# Volt_Measurement.net
KiCad netlist of a schematic drawn in Altium Designer
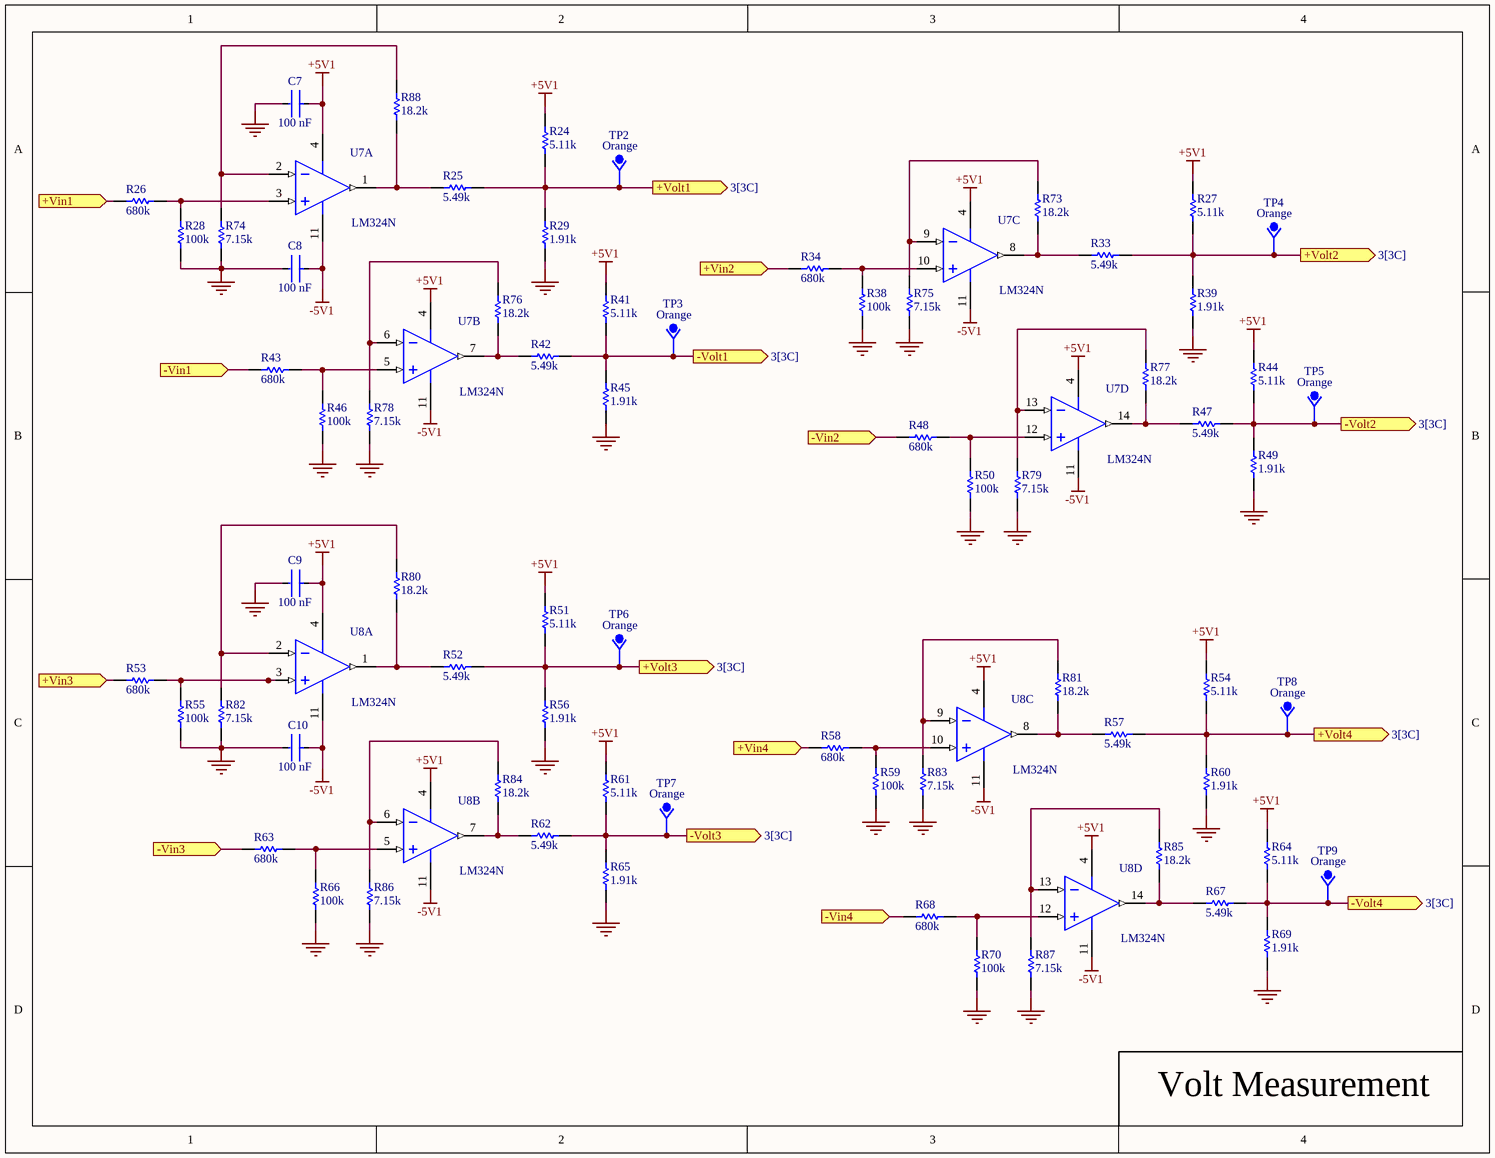
[diagram p0: Volt_Measurement.SchDoc]

(export (version "E")
  (design (tool "Eeschema 10.0.6"))
  (components
    (comp (ref "C7")
      (value "100 nF")
      (footprint "FP-CC0805-0_85-MFG")
      (description "CAP CER 0.1UF 16V X7R 0805")
      (fields
        (field (name "MANUFACTURER PART NUMBER") "CC0805KRX7R7BB104")
        (field (name "MANUFACTURER") "Yageo")
      )
      (libsource (lib "Altium Content Vault") (part "11868f565c42a9108669ba33697ecf6"))
    )
    (comp (ref "C8")
      (value "100 nF")
      (footprint "FP-CC0805-0_85-MFG")
      (description "CAP CER 0.1UF 16V X7R 0805")
      (fields
        (field (name "MANUFACTURER PART NUMBER") "CC0805KRX7R7BB104")
        (field (name "MANUFACTURER") "Yageo")
      )
      (libsource (lib "Altium Content Vault") (part "11868f565c42a9108669ba33697ecf6"))
    )
    (comp (ref "C9")
      (value "100 nF")
      (footprint "FP-CC0805-0_85-MFG")
      (description "CAP CER 0.1UF 16V X7R 0805")
      (fields
        (field (name "MANUFACTURER PART NUMBER") "CC0805KRX7R7BB104")
        (field (name "MANUFACTURER") "Yageo")
      )
      (libsource (lib "Altium Content Vault") (part "11868f565c42a9108669ba33697ecf6"))
    )
    (comp (ref "C10")
      (value "100 nF")
      (footprint "FP-CC0805-0_85-MFG")
      (description "CAP CER 0.1UF 16V X7R 0805")
      (fields
        (field (name "MANUFACTURER PART NUMBER") "CC0805KRX7R7BB104")
        (field (name "MANUFACTURER") "Yageo")
      )
      (libsource (lib "Altium Content Vault") (part "11868f565c42a9108669ba33697ecf6"))
    )
    (comp (ref "R24")
      (value "5.11k")
      (footprint "0805 Res")
      (fields
        (field (name "MANUFACTURER") "Stackpole Electronics")
        (field (name "MANUFACTURER PART NUMBER") "RMCF0805FT5K11")
        (field (name "TOLERANCE") "1%")
        (field (name "PUBLISHER") "Altium Limited")
      )
      (libsource (lib "Miscellaneous Devices") (part "Res1"))
    )
    (comp (ref "R25")
      (value "5.49k")
      (footprint "0805 Res")
      (fields
        (field (name "MANUFACTURER") "Stackpole Electronics")
        (field (name "MANUFACTURER PART NUMBER") "RMCF0805FT5K49")
        (field (name "TOLERANCE") "1%")
        (field (name "PUBLISHER") "Altium Limited")
      )
      (libsource (lib "Miscellaneous Devices") (part "Res1"))
    )
    (comp (ref "R26")
      (value "680k")
      (footprint "0805 Res")
      (fields
        (field (name "MANUFACTURER") "Stackpole Electronics")
        (field (name "MANUFACTURER PART NUMBER") "RMCF0805FT680K")
        (field (name "TOLERANCE") "1%")
        (field (name "PUBLISHER") "Altium Limited")
      )
      (libsource (lib "Miscellaneous Devices") (part "Res1"))
    )
    (comp (ref "R27")
      (value "5.11k")
      (footprint "0805 Res")
      (fields
        (field (name "MANUFACTURER") "Stackpole Electronics")
        (field (name "MANUFACTURER PART NUMBER") "RMCF0805FT5K11")
        (field (name "TOLERANCE") "1%")
        (field (name "PUBLISHER") "Altium Limited")
      )
      (libsource (lib "Miscellaneous Devices") (part "Res1"))
    )
    (comp (ref "R28")
      (value "100k")
      (footprint "0805 Res")
      (fields
        (field (name "MANUFACTURER") "Stackpole Electronics")
        (field (name "MANUFACTURER PART NUMBER") "RMCF0805FT100K")
        (field (name "TOLERANCE") "1%")
        (field (name "PUBLISHER") "Altium Limited")
      )
      (libsource (lib "Miscellaneous Devices") (part "Res1"))
    )
    (comp (ref "R29")
      (value "1.91k")
      (footprint "0805 Res")
      (fields
        (field (name "MANUFACTURER") "Stackpole Electronics")
        (field (name "MANUFACTURER PART NUMBER") "RMCF0805FT1K91")
        (field (name "TOLERANCE") "1%")
        (field (name "PUBLISHER") "Altium Limited")
      )
      (libsource (lib "Miscellaneous Devices") (part "Res1"))
    )
    (comp (ref "R33")
      (value "5.49k")
      (footprint "0805 Res")
      (fields
        (field (name "MANUFACTURER") "Stackpole Electronics")
        (field (name "MANUFACTURER PART NUMBER") "RMCF0805FT5K49")
        (field (name "TOLERANCE") "1%")
        (field (name "PUBLISHER") "Altium Limited")
      )
      (libsource (lib "Miscellaneous Devices") (part "Res1"))
    )
    (comp (ref "R34")
      (value "680k")
      (footprint "0805 Res")
      (fields
        (field (name "MANUFACTURER") "Stackpole Electronics")
        (field (name "MANUFACTURER PART NUMBER") "RMCF0805FT680K")
        (field (name "TOLERANCE") "1%")
        (field (name "PUBLISHER") "Altium Limited")
      )
      (libsource (lib "Miscellaneous Devices") (part "Res1"))
    )
    (comp (ref "R38")
      (value "100k")
      (footprint "0805 Res")
      (fields
        (field (name "MANUFACTURER") "Stackpole Electronics")
        (field (name "MANUFACTURER PART NUMBER") "RMCF0805FT100K")
        (field (name "TOLERANCE") "1%")
        (field (name "PUBLISHER") "Altium Limited")
      )
      (libsource (lib "Miscellaneous Devices") (part "Res1"))
    )
    (comp (ref "R39")
      (value "1.91k")
      (footprint "0805 Res")
      (fields
        (field (name "MANUFACTURER") "Stackpole Electronics")
        (field (name "MANUFACTURER PART NUMBER") "RMCF0805FT1K91")
        (field (name "TOLERANCE") "1%")
        (field (name "PUBLISHER") "Altium Limited")
      )
      (libsource (lib "Miscellaneous Devices") (part "Res1"))
    )
    (comp (ref "R41")
      (value "5.11k")
      (footprint "0805 Res")
      (fields
        (field (name "MANUFACTURER") "Stackpole Electronics")
        (field (name "MANUFACTURER PART NUMBER") "RMCF0805FT5K11")
        (field (name "TOLERANCE") "1%")
        (field (name "PUBLISHER") "Altium Limited")
      )
      (libsource (lib "Miscellaneous Devices") (part "Res1"))
    )
    (comp (ref "R42")
      (value "5.49k")
      (footprint "0805 Res")
      (fields
        (field (name "MANUFACTURER") "Stackpole Electronics")
        (field (name "MANUFACTURER PART NUMBER") "RMCF0805FT5K49")
        (field (name "TOLERANCE") "1%")
        (field (name "PUBLISHER") "Altium Limited")
      )
      (libsource (lib "Miscellaneous Devices") (part "Res1"))
    )
    (comp (ref "R43")
      (value "680k")
      (footprint "0805 Res")
      (fields
        (field (name "MANUFACTURER") "Stackpole Electronics")
        (field (name "MANUFACTURER PART NUMBER") "RMCF0805FT680K")
        (field (name "TOLERANCE") "1%")
        (field (name "PUBLISHER") "Altium Limited")
      )
      (libsource (lib "Miscellaneous Devices") (part "Res1"))
    )
    (comp (ref "R44")
      (value "5.11k")
      (footprint "0805 Res")
      (fields
        (field (name "MANUFACTURER") "Stackpole Electronics")
        (field (name "MANUFACTURER PART NUMBER") "RMCF0805FT5K11")
        (field (name "TOLERANCE") "1%")
        (field (name "PUBLISHER") "Altium Limited")
      )
      (libsource (lib "Miscellaneous Devices") (part "Res1"))
    )
    (comp (ref "R45")
      (value "1.91k")
      (footprint "0805 Res")
      (fields
        (field (name "MANUFACTURER") "Stackpole Electronics")
        (field (name "MANUFACTURER PART NUMBER") "RMCF0805FT1K91")
        (field (name "TOLERANCE") "1%")
        (field (name "PUBLISHER") "Altium Limited")
      )
      (libsource (lib "Miscellaneous Devices") (part "Res1"))
    )
    (comp (ref "R46")
      (value "100k")
      (footprint "0805 Res")
      (fields
        (field (name "MANUFACTURER") "Stackpole Electronics")
        (field (name "MANUFACTURER PART NUMBER") "RMCF0805FT100K")
        (field (name "TOLERANCE") "1%")
        (field (name "PUBLISHER") "Altium Limited")
      )
      (libsource (lib "Miscellaneous Devices") (part "Res1"))
    )
    (comp (ref "R47")
      (value "5.49k")
      (footprint "0805 Res")
      (fields
        (field (name "MANUFACTURER") "Stackpole Electronics")
        (field (name "MANUFACTURER PART NUMBER") "RMCF0805FT5K49")
        (field (name "TOLERANCE") "1%")
        (field (name "PUBLISHER") "Altium Limited")
      )
      (libsource (lib "Miscellaneous Devices") (part "Res1"))
    )
    (comp (ref "R48")
      (value "680k")
      (footprint "0805 Res")
      (fields
        (field (name "MANUFACTURER") "Stackpole Electronics")
        (field (name "MANUFACTURER PART NUMBER") "RMCF0805FT680K")
        (field (name "TOLERANCE") "1%")
        (field (name "PUBLISHER") "Altium Limited")
      )
      (libsource (lib "Miscellaneous Devices") (part "Res1"))
    )
    (comp (ref "R49")
      (value "1.91k")
      (footprint "0805 Res")
      (fields
        (field (name "MANUFACTURER") "Stackpole Electronics")
        (field (name "MANUFACTURER PART NUMBER") "RMCF0805FT1K91")
        (field (name "TOLERANCE") "1%")
        (field (name "PUBLISHER") "Altium Limited")
      )
      (libsource (lib "Miscellaneous Devices") (part "Res1"))
    )
    (comp (ref "R50")
      (value "100k")
      (footprint "0805 Res")
      (fields
        (field (name "MANUFACTURER") "Stackpole Electronics")
        (field (name "MANUFACTURER PART NUMBER") "RMCF0805FT100K")
        (field (name "TOLERANCE") "1%")
        (field (name "PUBLISHER") "Altium Limited")
      )
      (libsource (lib "Miscellaneous Devices") (part "Res1"))
    )
    (comp (ref "R51")
      (value "5.11k")
      (footprint "0805 Res")
      (fields
        (field (name "MANUFACTURER") "Stackpole Electronics")
        (field (name "MANUFACTURER PART NUMBER") "RMCF0805FT5K11")
        (field (name "TOLERANCE") "1%")
        (field (name "PUBLISHER") "Altium Limited")
      )
      (libsource (lib "Miscellaneous Devices") (part "Res1"))
    )
    (comp (ref "R52")
      (value "5.49k")
      (footprint "0805 Res")
      (fields
        (field (name "MANUFACTURER") "Stackpole Electronics")
        (field (name "MANUFACTURER PART NUMBER") "RMCF0805FT5K49")
        (field (name "TOLERANCE") "1%")
        (field (name "PUBLISHER") "Altium Limited")
      )
      (libsource (lib "Miscellaneous Devices") (part "Res1"))
    )
    (comp (ref "R53")
      (value "680k")
      (footprint "0805 Res")
      (fields
        (field (name "MANUFACTURER") "Stackpole Electronics")
        (field (name "MANUFACTURER PART NUMBER") "RMCF0805FT680K")
        (field (name "TOLERANCE") "1%")
        (field (name "PUBLISHER") "Altium Limited")
      )
      (libsource (lib "Miscellaneous Devices") (part "Res1"))
    )
    (comp (ref "R54")
      (value "5.11k")
      (footprint "0805 Res")
      (fields
        (field (name "MANUFACTURER") "Stackpole Electronics")
        (field (name "MANUFACTURER PART NUMBER") "RMCF0805FT5K11")
        (field (name "TOLERANCE") "1%")
        (field (name "PUBLISHER") "Altium Limited")
      )
      (libsource (lib "Miscellaneous Devices") (part "Res1"))
    )
    (comp (ref "R55")
      (value "100k")
      (footprint "0805 Res")
      (fields
        (field (name "MANUFACTURER") "Stackpole Electronics")
        (field (name "MANUFACTURER PART NUMBER") "RMCF0805FT100K")
        (field (name "TOLERANCE") "1%")
        (field (name "PUBLISHER") "Altium Limited")
      )
      (libsource (lib "Miscellaneous Devices") (part "Res1"))
    )
    (comp (ref "R56")
      (value "1.91k")
      (footprint "0805 Res")
      (fields
        (field (name "MANUFACTURER") "Stackpole Electronics")
        (field (name "MANUFACTURER PART NUMBER") "RMCF0805FT1K91")
        (field (name "TOLERANCE") "1%")
        (field (name "PUBLISHER") "Altium Limited")
      )
      (libsource (lib "Miscellaneous Devices") (part "Res1"))
    )
    (comp (ref "R57")
      (value "5.49k")
      (footprint "0805 Res")
      (fields
        (field (name "MANUFACTURER") "Stackpole Electronics")
        (field (name "MANUFACTURER PART NUMBER") "RMCF0805FT5K49")
        (field (name "TOLERANCE") "1%")
        (field (name "PUBLISHER") "Altium Limited")
      )
      (libsource (lib "Miscellaneous Devices") (part "Res1"))
    )
    (comp (ref "R58")
      (value "680k")
      (footprint "0805 Res")
      (fields
        (field (name "MANUFACTURER") "Stackpole Electronics")
        (field (name "MANUFACTURER PART NUMBER") "RMCF0805FT680K")
        (field (name "TOLERANCE") "1%")
        (field (name "PUBLISHER") "Altium Limited")
      )
      (libsource (lib "Miscellaneous Devices") (part "Res1"))
    )
    (comp (ref "R59")
      (value "100k")
      (footprint "0805 Res")
      (fields
        (field (name "MANUFACTURER") "Stackpole Electronics")
        (field (name "MANUFACTURER PART NUMBER") "RMCF0805FT100K")
        (field (name "TOLERANCE") "1%")
        (field (name "PUBLISHER") "Altium Limited")
      )
      (libsource (lib "Miscellaneous Devices") (part "Res1"))
    )
    (comp (ref "R60")
      (value "1.91k")
      (footprint "0805 Res")
      (fields
        (field (name "MANUFACTURER") "Stackpole Electronics")
        (field (name "MANUFACTURER PART NUMBER") "RMCF0805FT1K91")
        (field (name "TOLERANCE") "1%")
        (field (name "PUBLISHER") "Altium Limited")
      )
      (libsource (lib "Miscellaneous Devices") (part "Res1"))
    )
    (comp (ref "R61")
      (value "5.11k")
      (footprint "0805 Res")
      (fields
        (field (name "MANUFACTURER") "Stackpole Electronics")
        (field (name "MANUFACTURER PART NUMBER") "RMCF0805FT5K11")
        (field (name "TOLERANCE") "1%")
        (field (name "PUBLISHER") "Altium Limited")
      )
      (libsource (lib "Miscellaneous Devices") (part "Res1"))
    )
    (comp (ref "R62")
      (value "5.49k")
      (footprint "0805 Res")
      (fields
        (field (name "MANUFACTURER") "Stackpole Electronics")
        (field (name "MANUFACTURER PART NUMBER") "RMCF0805FT5K49")
        (field (name "TOLERANCE") "1%")
        (field (name "PUBLISHER") "Altium Limited")
      )
      (libsource (lib "Miscellaneous Devices") (part "Res1"))
    )
    (comp (ref "R63")
      (value "680k")
      (footprint "0805 Res")
      (fields
        (field (name "MANUFACTURER") "Stackpole Electronics")
        (field (name "MANUFACTURER PART NUMBER") "RMCF0805FT680K")
        (field (name "TOLERANCE") "1%")
        (field (name "PUBLISHER") "Altium Limited")
      )
      (libsource (lib "Miscellaneous Devices") (part "Res1"))
    )
    (comp (ref "R64")
      (value "5.11k")
      (footprint "0805 Res")
      (fields
        (field (name "MANUFACTURER") "Stackpole Electronics")
        (field (name "MANUFACTURER PART NUMBER") "RMCF0805FT5K11")
        (field (name "TOLERANCE") "1%")
        (field (name "PUBLISHER") "Altium Limited")
      )
      (libsource (lib "Miscellaneous Devices") (part "Res1"))
    )
    (comp (ref "R65")
      (value "1.91k")
      (footprint "0805 Res")
      (fields
        (field (name "MANUFACTURER") "Stackpole Electronics")
        (field (name "MANUFACTURER PART NUMBER") "RMCF0805FT1K91")
        (field (name "TOLERANCE") "1%")
        (field (name "PUBLISHER") "Altium Limited")
      )
      (libsource (lib "Miscellaneous Devices") (part "Res1"))
    )
    (comp (ref "R66")
      (value "100k")
      (footprint "0805 Res")
      (fields
        (field (name "MANUFACTURER") "Stackpole Electronics")
        (field (name "MANUFACTURER PART NUMBER") "RMCF0805FT100K")
        (field (name "TOLERANCE") "1%")
        (field (name "PUBLISHER") "Altium Limited")
      )
      (libsource (lib "Miscellaneous Devices") (part "Res1"))
    )
    (comp (ref "R67")
      (value "5.49k")
      (footprint "0805 Res")
      (fields
        (field (name "MANUFACTURER") "Stackpole Electronics")
        (field (name "MANUFACTURER PART NUMBER") "RMCF0805FT5K49")
        (field (name "TOLERANCE") "1%")
        (field (name "PUBLISHER") "Altium Limited")
      )
      (libsource (lib "Miscellaneous Devices") (part "Res1"))
    )
    (comp (ref "R68")
      (value "680k")
      (footprint "0805 Res")
      (fields
        (field (name "MANUFACTURER") "Stackpole Electronics")
        (field (name "MANUFACTURER PART NUMBER") "RMCF0805FT680K")
        (field (name "TOLERANCE") "1%")
        (field (name "PUBLISHER") "Altium Limited")
      )
      (libsource (lib "Miscellaneous Devices") (part "Res1"))
    )
    (comp (ref "R69")
      (value "1.91k")
      (footprint "0805 Res")
      (fields
        (field (name "MANUFACTURER") "Stackpole Electronics")
        (field (name "MANUFACTURER PART NUMBER") "RMCF0805FT1K91")
        (field (name "TOLERANCE") "1%")
        (field (name "PUBLISHER") "Altium Limited")
      )
      (libsource (lib "Miscellaneous Devices") (part "Res1"))
    )
    (comp (ref "R70")
      (value "100k")
      (footprint "0805 Res")
      (fields
        (field (name "MANUFACTURER") "Stackpole Electronics")
        (field (name "MANUFACTURER PART NUMBER") "RMCF0805FT100K")
        (field (name "TOLERANCE") "1%")
        (field (name "PUBLISHER") "Altium Limited")
      )
      (libsource (lib "Miscellaneous Devices") (part "Res1"))
    )
    (comp (ref "R73")
      (value "18.2k")
      (footprint "0805 Res")
      (fields
        (field (name "MANUFACTURER") "Stackpole Electronics")
        (field (name "MANUFACTURER PART NUMBER") "RMCF0805FT18K2")
        (field (name "TOLERANCE") "1%")
        (field (name "PUBLISHER") "Altium Limited")
      )
      (libsource (lib "Miscellaneous Devices") (part "Res1"))
    )
    (comp (ref "R74")
      (value "7.15k")
      (footprint "0805 Res")
      (fields
        (field (name "MANUFACTURER") "Stackpole Electronics")
        (field (name "MANUFACTURER PART NUMBER") "RMCF0805FT7K15")
        (field (name "TOLERANCE") "1%")
        (field (name "PUBLISHER") "Altium Limited")
      )
      (libsource (lib "Miscellaneous Devices") (part "Res1"))
    )
    (comp (ref "R75")
      (value "7.15k")
      (footprint "0805 Res")
      (fields
        (field (name "MANUFACTURER") "Stackpole Electronics")
        (field (name "MANUFACTURER PART NUMBER") "RMCF0805FT7K15")
        (field (name "TOLERANCE") "1%")
        (field (name "PUBLISHER") "Altium Limited")
      )
      (libsource (lib "Miscellaneous Devices") (part "Res1"))
    )
    (comp (ref "R76")
      (value "18.2k")
      (footprint "0805 Res")
      (fields
        (field (name "MANUFACTURER") "Stackpole Electronics")
        (field (name "MANUFACTURER PART NUMBER") "RMCF0805FT18K2")
        (field (name "TOLERANCE") "1%")
        (field (name "PUBLISHER") "Altium Limited")
      )
      (libsource (lib "Miscellaneous Devices") (part "Res1"))
    )
    (comp (ref "R77")
      (value "18.2k")
      (footprint "0805 Res")
      (fields
        (field (name "MANUFACTURER") "Stackpole Electronics")
        (field (name "MANUFACTURER PART NUMBER") "RMCF0805FT18K2")
        (field (name "TOLERANCE") "1%")
        (field (name "PUBLISHER") "Altium Limited")
      )
      (libsource (lib "Miscellaneous Devices") (part "Res1"))
    )
    (comp (ref "R78")
      (value "7.15k")
      (footprint "0805 Res")
      (fields
        (field (name "MANUFACTURER") "Stackpole Electronics")
        (field (name "MANUFACTURER PART NUMBER") "RMCF0805FT7K15")
        (field (name "TOLERANCE") "1%")
        (field (name "PUBLISHER") "Altium Limited")
      )
      (libsource (lib "Miscellaneous Devices") (part "Res1"))
    )
    (comp (ref "R79")
      (value "7.15k")
      (footprint "0805 Res")
      (fields
        (field (name "MANUFACTURER") "Stackpole Electronics")
        (field (name "MANUFACTURER PART NUMBER") "RMCF0805FT7K15")
        (field (name "TOLERANCE") "1%")
        (field (name "PUBLISHER") "Altium Limited")
      )
      (libsource (lib "Miscellaneous Devices") (part "Res1"))
    )
    (comp (ref "R80")
      (value "18.2k")
      (footprint "0805 Res")
      (fields
        (field (name "MANUFACTURER") "Stackpole Electronics")
        (field (name "MANUFACTURER PART NUMBER") "RMCF0805FT18K2")
        (field (name "TOLERANCE") "1%")
        (field (name "PUBLISHER") "Altium Limited")
      )
      (libsource (lib "Miscellaneous Devices") (part "Res1"))
    )
    (comp (ref "R81")
      (value "18.2k")
      (footprint "0805 Res")
      (fields
        (field (name "MANUFACTURER") "Stackpole Electronics")
        (field (name "MANUFACTURER PART NUMBER") "RMCF0805FT18K2")
        (field (name "TOLERANCE") "1%")
        (field (name "PUBLISHER") "Altium Limited")
      )
      (libsource (lib "Miscellaneous Devices") (part "Res1"))
    )
    (comp (ref "R82")
      (value "7.15k")
      (footprint "0805 Res")
      (fields
        (field (name "MANUFACTURER") "Stackpole Electronics")
        (field (name "MANUFACTURER PART NUMBER") "RMCF0805FT7K15")
        (field (name "TOLERANCE") "1%")
        (field (name "PUBLISHER") "Altium Limited")
      )
      (libsource (lib "Miscellaneous Devices") (part "Res1"))
    )
    (comp (ref "R83")
      (value "7.15k")
      (footprint "0805 Res")
      (fields
        (field (name "MANUFACTURER") "Stackpole Electronics")
        (field (name "MANUFACTURER PART NUMBER") "RMCF0805FT7K15")
        (field (name "TOLERANCE") "1%")
        (field (name "PUBLISHER") "Altium Limited")
      )
      (libsource (lib "Miscellaneous Devices") (part "Res1"))
    )
    (comp (ref "R84")
      (value "18.2k")
      (footprint "0805 Res")
      (fields
        (field (name "MANUFACTURER") "Stackpole Electronics")
        (field (name "MANUFACTURER PART NUMBER") "RMCF0805FT18K2")
        (field (name "TOLERANCE") "1%")
        (field (name "PUBLISHER") "Altium Limited")
      )
      (libsource (lib "Miscellaneous Devices") (part "Res1"))
    )
    (comp (ref "R85")
      (value "18.2k")
      (footprint "0805 Res")
      (fields
        (field (name "MANUFACTURER") "Stackpole Electronics")
        (field (name "MANUFACTURER PART NUMBER") "RMCF0805FT18K2")
        (field (name "TOLERANCE") "1%")
        (field (name "PUBLISHER") "Altium Limited")
      )
      (libsource (lib "Miscellaneous Devices") (part "Res1"))
    )
    (comp (ref "R86")
      (value "7.15k")
      (footprint "0805 Res")
      (fields
        (field (name "MANUFACTURER") "Stackpole Electronics")
        (field (name "MANUFACTURER PART NUMBER") "RMCF0805FT7K15")
        (field (name "TOLERANCE") "1%")
        (field (name "PUBLISHER") "Altium Limited")
      )
      (libsource (lib "Miscellaneous Devices") (part "Res1"))
    )
    (comp (ref "R87")
      (value "7.15k")
      (footprint "0805 Res")
      (fields
        (field (name "MANUFACTURER") "Stackpole Electronics")
        (field (name "MANUFACTURER PART NUMBER") "RMCF0805FT7K15")
        (field (name "TOLERANCE") "1%")
        (field (name "PUBLISHER") "Altium Limited")
      )
      (libsource (lib "Miscellaneous Devices") (part "Res1"))
    )
    (comp (ref "R88")
      (value "18.2k")
      (footprint "0805 Res")
      (fields
        (field (name "MANUFACTURER") "Stackpole Electronics")
        (field (name "MANUFACTURER PART NUMBER") "RMCF0805FT18K2")
        (field (name "TOLERANCE") "1%")
        (field (name "PUBLISHER") "Altium Limited")
      )
      (libsource (lib "Miscellaneous Devices") (part "Res1"))
    )
    (comp (ref "TP2")
      (value "TP (Orange)")
      (footprint "ORANGETP")
      (description "Orange Test Point")
      (fields
        (field (name "MANUFACTURER") "Keystone")
        (field (name "MANUFACTURER PART NUMBER") "5003")
        (field (name "COLOR") "Orange")
      )
      (libsource (lib "*") (part "TP"))
    )
    (comp (ref "TP3")
      (value "TP (Orange)")
      (footprint "ORANGETP")
      (description "Orange Test Point")
      (fields
        (field (name "MANUFACTURER") "Keystone")
        (field (name "MANUFACTURER PART NUMBER") "5003")
        (field (name "COLOR") "Orange")
      )
      (libsource (lib "*") (part "TP"))
    )
    (comp (ref "TP4")
      (value "TP (Orange)")
      (footprint "ORANGETP")
      (description "Orange Test Point")
      (fields
        (field (name "MANUFACTURER") "Keystone")
        (field (name "MANUFACTURER PART NUMBER") "5003")
        (field (name "COLOR") "Orange")
      )
      (libsource (lib "*") (part "TP"))
    )
    (comp (ref "TP5")
      (value "TP (Orange)")
      (footprint "ORANGETP")
      (description "Orange Test Point")
      (fields
        (field (name "MANUFACTURER") "Keystone")
        (field (name "MANUFACTURER PART NUMBER") "5003")
        (field (name "COLOR") "Orange")
      )
      (libsource (lib "*") (part "TP"))
    )
    (comp (ref "TP6")
      (value "TP (Orange)")
      (footprint "ORANGETP")
      (description "Orange Test Point")
      (fields
        (field (name "MANUFACTURER") "Keystone")
        (field (name "MANUFACTURER PART NUMBER") "5003")
        (field (name "COLOR") "Orange")
      )
      (libsource (lib "*") (part "TP"))
    )
    (comp (ref "TP7")
      (value "TP (Orange)")
      (footprint "ORANGETP")
      (description "Orange Test Point")
      (fields
        (field (name "MANUFACTURER") "Keystone")
        (field (name "MANUFACTURER PART NUMBER") "5003")
        (field (name "COLOR") "Orange")
      )
      (libsource (lib "*") (part "TP"))
    )
    (comp (ref "TP8")
      (value "TP (Orange)")
      (footprint "ORANGETP")
      (description "Orange Test Point")
      (fields
        (field (name "MANUFACTURER") "Keystone")
        (field (name "MANUFACTURER PART NUMBER") "5003")
        (field (name "COLOR") "Orange")
      )
      (libsource (lib "*") (part "TP"))
    )
    (comp (ref "TP9")
      (value "TP (Orange)")
      (footprint "ORANGETP")
      (description "Orange Test Point")
      (fields
        (field (name "MANUFACTURER") "Keystone")
        (field (name "MANUFACTURER PART NUMBER") "5003")
        (field (name "COLOR") "Orange")
      )
      (libsource (lib "*") (part "TP"))
    )
    (comp (ref "U7")
      (value "4CH Op-Amp")
      (footprint "N0014A")
      (description "Low Power Quad Operational Amplifier, 14-pin MDIP")
      (fields
        (field (name "MANUFACTURER") "Texas Instruments")
        (field (name "MANUFACTURER PART NUMBER") "LM324N")
      )
      (libsource (lib "Altium Content Vault") (part "AMP-OPA-LM124-14"))
    )
    (comp (ref "U8")
      (value "4CH Op-Amp")
      (footprint "N0014A")
      (description "Low Power Quad Operational Amplifier, 14-pin MDIP")
      (fields
        (field (name "MANUFACTURER") "Texas Instruments")
        (field (name "MANUFACTURER PART NUMBER") "LM324N")
      )
      (libsource (lib "Altium Content Vault") (part "AMP-OPA-LM124-14"))
    )
  )
  (nets
    (net (code "1") (name "+5V1") (class "Default")
      (node (ref "C7") (pin "1") (pinfunction "1_1") (pintype "passive"))
      (node (ref "C9") (pin "1") (pinfunction "1_1") (pintype "passive"))
      (node (ref "R24") (pin "2") (pinfunction "2_2") (pintype "passive"))
      (node (ref "R27") (pin "2") (pinfunction "2_2") (pintype "passive"))
      (node (ref "R41") (pin "2") (pinfunction "2_2") (pintype "passive"))
      (node (ref "R44") (pin "2") (pinfunction "2_2") (pintype "passive"))
      (node (ref "R51") (pin "2") (pinfunction "2_2") (pintype "passive"))
      (node (ref "R54") (pin "2") (pinfunction "2_2") (pintype "passive"))
      (node (ref "R61") (pin "2") (pinfunction "2_2") (pintype "passive"))
      (node (ref "R64") (pin "2") (pinfunction "2_2") (pintype "passive"))
      (node (ref "U7") (pin "4") (pinfunction "V+_4") (pintype "power_in"))
      (node (ref "U8") (pin "4") (pinfunction "V+_4") (pintype "power_in"))
    )
    (net (code "2") (name "-5V1") (class "Default")
      (node (ref "C10") (pin "1") (pinfunction "1_1") (pintype "passive"))
      (node (ref "C8") (pin "1") (pinfunction "1_1") (pintype "passive"))
      (node (ref "U7") (pin "11") (pinfunction "GND_11") (pintype "power_in"))
      (node (ref "U8") (pin "11") (pinfunction "GND_11") (pintype "power_in"))
    )
    (net (code "3") (name "/+Vin1") (class "Default")
      (node (ref "R26") (pin "1") (pinfunction "1_1") (pintype "passive"))
    )
    (net (code "4") (name "/+Vin2") (class "Default")
      (node (ref "R34") (pin "1") (pinfunction "1_1") (pintype "passive"))
    )
    (net (code "5") (name "/+Vin3") (class "Default")
      (node (ref "R53") (pin "1") (pinfunction "1_1") (pintype "passive"))
    )
    (net (code "6") (name "/+Vin4") (class "Default")
      (node (ref "R58") (pin "1") (pinfunction "1_1") (pintype "passive"))
    )
    (net (code "7") (name "/+Volt1") (class "Default")
      (node (ref "R24") (pin "1") (pinfunction "1_1") (pintype "passive"))
      (node (ref "R25") (pin "2") (pinfunction "2_2") (pintype "passive"))
      (node (ref "R29") (pin "2") (pinfunction "2_2") (pintype "passive"))
      (node (ref "TP2") (pin "1") (pinfunction "TP_1") (pintype "passive"))
    )
    (net (code "8") (name "/+Volt2") (class "Default")
      (node (ref "R27") (pin "1") (pinfunction "1_1") (pintype "passive"))
      (node (ref "R33") (pin "2") (pinfunction "2_2") (pintype "passive"))
      (node (ref "R39") (pin "2") (pinfunction "2_2") (pintype "passive"))
      (node (ref "TP4") (pin "1") (pinfunction "TP_1") (pintype "passive"))
    )
    (net (code "9") (name "/+Volt3") (class "Default")
      (node (ref "R51") (pin "1") (pinfunction "1_1") (pintype "passive"))
      (node (ref "R52") (pin "2") (pinfunction "2_2") (pintype "passive"))
      (node (ref "R56") (pin "2") (pinfunction "2_2") (pintype "passive"))
      (node (ref "TP6") (pin "1") (pinfunction "TP_1") (pintype "passive"))
    )
    (net (code "10") (name "/+Volt4") (class "Default")
      (node (ref "R54") (pin "1") (pinfunction "1_1") (pintype "passive"))
      (node (ref "R57") (pin "2") (pinfunction "2_2") (pintype "passive"))
      (node (ref "R60") (pin "2") (pinfunction "2_2") (pintype "passive"))
      (node (ref "TP8") (pin "1") (pinfunction "TP_1") (pintype "passive"))
    )
    (net (code "11") (name "/-Vin1") (class "Default")
      (node (ref "R43") (pin "1") (pinfunction "1_1") (pintype "passive"))
    )
    (net (code "12") (name "/-Vin2") (class "Default")
      (node (ref "R48") (pin "1") (pinfunction "1_1") (pintype "passive"))
    )
    (net (code "13") (name "/-Vin3") (class "Default")
      (node (ref "R63") (pin "1") (pinfunction "1_1") (pintype "passive"))
    )
    (net (code "14") (name "/-Vin4") (class "Default")
      (node (ref "R68") (pin "1") (pinfunction "1_1") (pintype "passive"))
    )
    (net (code "15") (name "/-Volt1") (class "Default")
      (node (ref "R41") (pin "1") (pinfunction "1_1") (pintype "passive"))
      (node (ref "R42") (pin "2") (pinfunction "2_2") (pintype "passive"))
      (node (ref "R45") (pin "2") (pinfunction "2_2") (pintype "passive"))
      (node (ref "TP3") (pin "1") (pinfunction "TP_1") (pintype "passive"))
    )
    (net (code "16") (name "/-Volt2") (class "Default")
      (node (ref "R44") (pin "1") (pinfunction "1_1") (pintype "passive"))
      (node (ref "R47") (pin "2") (pinfunction "2_2") (pintype "passive"))
      (node (ref "R49") (pin "2") (pinfunction "2_2") (pintype "passive"))
      (node (ref "TP5") (pin "1") (pinfunction "TP_1") (pintype "passive"))
    )
    (net (code "17") (name "/-Volt3") (class "Default")
      (node (ref "R61") (pin "1") (pinfunction "1_1") (pintype "passive"))
      (node (ref "R62") (pin "2") (pinfunction "2_2") (pintype "passive"))
      (node (ref "R65") (pin "2") (pinfunction "2_2") (pintype "passive"))
      (node (ref "TP7") (pin "1") (pinfunction "TP_1") (pintype "passive"))
    )
    (net (code "18") (name "/-Volt4") (class "Default")
      (node (ref "R64") (pin "1") (pinfunction "1_1") (pintype "passive"))
      (node (ref "R67") (pin "2") (pinfunction "2_2") (pintype "passive"))
      (node (ref "R69") (pin "2") (pinfunction "2_2") (pintype "passive"))
      (node (ref "TP9") (pin "1") (pinfunction "TP_1") (pintype "passive"))
    )
    (net (code "19") (name "GND") (class "Default")
      (node (ref "C10") (pin "2") (pinfunction "2_2") (pintype "passive"))
      (node (ref "C7") (pin "2") (pinfunction "2_2") (pintype "passive"))
      (node (ref "C8") (pin "2") (pinfunction "2_2") (pintype "passive"))
      (node (ref "C9") (pin "2") (pinfunction "2_2") (pintype "passive"))
      (node (ref "R28") (pin "2") (pinfunction "2_2") (pintype "passive"))
      (node (ref "R29") (pin "1") (pinfunction "1_1") (pintype "passive"))
      (node (ref "R38") (pin "2") (pinfunction "2_2") (pintype "passive"))
      (node (ref "R39") (pin "1") (pinfunction "1_1") (pintype "passive"))
      (node (ref "R45") (pin "1") (pinfunction "1_1") (pintype "passive"))
      (node (ref "R46") (pin "2") (pinfunction "2_2") (pintype "passive"))
      (node (ref "R49") (pin "1") (pinfunction "1_1") (pintype "passive"))
      (node (ref "R50") (pin "2") (pinfunction "2_2") (pintype "passive"))
      (node (ref "R55") (pin "2") (pinfunction "2_2") (pintype "passive"))
      (node (ref "R56") (pin "1") (pinfunction "1_1") (pintype "passive"))
      (node (ref "R59") (pin "2") (pinfunction "2_2") (pintype "passive"))
      (node (ref "R60") (pin "1") (pinfunction "1_1") (pintype "passive"))
      (node (ref "R65") (pin "1") (pinfunction "1_1") (pintype "passive"))
      (node (ref "R66") (pin "2") (pinfunction "2_2") (pintype "passive"))
      (node (ref "R69") (pin "1") (pinfunction "1_1") (pintype "passive"))
      (node (ref "R70") (pin "2") (pinfunction "2_2") (pintype "passive"))
      (node (ref "R74") (pin "1") (pinfunction "1_1") (pintype "passive"))
      (node (ref "R75") (pin "1") (pinfunction "1_1") (pintype "passive"))
      (node (ref "R78") (pin "1") (pinfunction "1_1") (pintype "passive"))
      (node (ref "R79") (pin "1") (pinfunction "1_1") (pintype "passive"))
      (node (ref "R82") (pin "1") (pinfunction "1_1") (pintype "passive"))
      (node (ref "R83") (pin "1") (pinfunction "1_1") (pintype "passive"))
      (node (ref "R86") (pin "1") (pinfunction "1_1") (pintype "passive"))
      (node (ref "R87") (pin "1") (pinfunction "1_1") (pintype "passive"))
    )
    (net (code "20") (name "Net-(U7A-IN1+)") (class "Default")
      (node (ref "R26") (pin "2") (pinfunction "2_2") (pintype "passive"))
      (node (ref "R28") (pin "1") (pinfunction "1_1") (pintype "passive"))
      (node (ref "U7") (pin "3") (pinfunction "IN1+_3") (pintype "input"))
    )
    (net (code "21") (name "Net-(U7A-IN1-)") (class "Default")
      (node (ref "R74") (pin "2") (pinfunction "2_2") (pintype "passive"))
      (node (ref "R88") (pin "2") (pinfunction "2_2") (pintype "passive"))
      (node (ref "U7") (pin "2") (pinfunction "IN1-_2") (pintype "input"))
    )
    (net (code "22") (name "Net-(U7A-OUT1)") (class "Default")
      (node (ref "R25") (pin "1") (pinfunction "1_1") (pintype "passive"))
      (node (ref "R88") (pin "1") (pinfunction "1_1") (pintype "passive"))
      (node (ref "U7") (pin "1") (pinfunction "OUT1_1") (pintype "output"))
    )
    (net (code "23") (name "Net-(U7B-IN2+)") (class "Default")
      (node (ref "R43") (pin "2") (pinfunction "2_2") (pintype "passive"))
      (node (ref "R46") (pin "1") (pinfunction "1_1") (pintype "passive"))
      (node (ref "U7") (pin "5") (pinfunction "IN2+_5") (pintype "input"))
    )
    (net (code "24") (name "Net-(U7B-IN2-)") (class "Default")
      (node (ref "R76") (pin "2") (pinfunction "2_2") (pintype "passive"))
      (node (ref "R78") (pin "2") (pinfunction "2_2") (pintype "passive"))
      (node (ref "U7") (pin "6") (pinfunction "IN2-_6") (pintype "input"))
    )
    (net (code "25") (name "Net-(U7B-OUT2)") (class "Default")
      (node (ref "R42") (pin "1") (pinfunction "1_1") (pintype "passive"))
      (node (ref "R76") (pin "1") (pinfunction "1_1") (pintype "passive"))
      (node (ref "U7") (pin "7") (pinfunction "OUT2_7") (pintype "output"))
    )
    (net (code "26") (name "Net-(U7C-IN3+)") (class "Default")
      (node (ref "R34") (pin "2") (pinfunction "2_2") (pintype "passive"))
      (node (ref "R38") (pin "1") (pinfunction "1_1") (pintype "passive"))
      (node (ref "U7") (pin "10") (pinfunction "IN3+_10") (pintype "input"))
    )
    (net (code "27") (name "Net-(U7C-IN3-)") (class "Default")
      (node (ref "R73") (pin "2") (pinfunction "2_2") (pintype "passive"))
      (node (ref "R75") (pin "2") (pinfunction "2_2") (pintype "passive"))
      (node (ref "U7") (pin "9") (pinfunction "IN3-_9") (pintype "input"))
    )
    (net (code "28") (name "Net-(U7C-OUT3)") (class "Default")
      (node (ref "R33") (pin "1") (pinfunction "1_1") (pintype "passive"))
      (node (ref "R73") (pin "1") (pinfunction "1_1") (pintype "passive"))
      (node (ref "U7") (pin "8") (pinfunction "OUT3_8") (pintype "output"))
    )
    (net (code "29") (name "Net-(U7D-IN4+)") (class "Default")
      (node (ref "R48") (pin "2") (pinfunction "2_2") (pintype "passive"))
      (node (ref "R50") (pin "1") (pinfunction "1_1") (pintype "passive"))
      (node (ref "U7") (pin "12") (pinfunction "IN4+_12") (pintype "input"))
    )
    (net (code "30") (name "Net-(U7D-IN4-)") (class "Default")
      (node (ref "R77") (pin "2") (pinfunction "2_2") (pintype "passive"))
      (node (ref "R79") (pin "2") (pinfunction "2_2") (pintype "passive"))
      (node (ref "U7") (pin "13") (pinfunction "IN4-_13") (pintype "input"))
    )
    (net (code "31") (name "Net-(U7D-OUT4)") (class "Default")
      (node (ref "R47") (pin "1") (pinfunction "1_1") (pintype "passive"))
      (node (ref "R77") (pin "1") (pinfunction "1_1") (pintype "passive"))
      (node (ref "U7") (pin "14") (pinfunction "OUT4_14") (pintype "output"))
    )
    (net (code "32") (name "Net-(U8A-IN1+)") (class "Default")
      (node (ref "R53") (pin "2") (pinfunction "2_2") (pintype "passive"))
      (node (ref "R55") (pin "1") (pinfunction "1_1") (pintype "passive"))
      (node (ref "U8") (pin "3") (pinfunction "IN1+_3") (pintype "input"))
    )
    (net (code "33") (name "Net-(U8A-IN1-)") (class "Default")
      (node (ref "R80") (pin "2") (pinfunction "2_2") (pintype "passive"))
      (node (ref "R82") (pin "2") (pinfunction "2_2") (pintype "passive"))
      (node (ref "U8") (pin "2") (pinfunction "IN1-_2") (pintype "input"))
    )
    (net (code "34") (name "Net-(U8A-OUT1)") (class "Default")
      (node (ref "R52") (pin "1") (pinfunction "1_1") (pintype "passive"))
      (node (ref "R80") (pin "1") (pinfunction "1_1") (pintype "passive"))
      (node (ref "U8") (pin "1") (pinfunction "OUT1_1") (pintype "output"))
    )
    (net (code "35") (name "Net-(U8B-IN2+)") (class "Default")
      (node (ref "R63") (pin "2") (pinfunction "2_2") (pintype "passive"))
      (node (ref "R66") (pin "1") (pinfunction "1_1") (pintype "passive"))
      (node (ref "U8") (pin "5") (pinfunction "IN2+_5") (pintype "input"))
    )
    (net (code "36") (name "Net-(U8B-IN2-)") (class "Default")
      (node (ref "R84") (pin "2") (pinfunction "2_2") (pintype "passive"))
      (node (ref "R86") (pin "2") (pinfunction "2_2") (pintype "passive"))
      (node (ref "U8") (pin "6") (pinfunction "IN2-_6") (pintype "input"))
    )
    (net (code "37") (name "Net-(U8B-OUT2)") (class "Default")
      (node (ref "R62") (pin "1") (pinfunction "1_1") (pintype "passive"))
      (node (ref "R84") (pin "1") (pinfunction "1_1") (pintype "passive"))
      (node (ref "U8") (pin "7") (pinfunction "OUT2_7") (pintype "output"))
    )
    (net (code "38") (name "Net-(U8C-IN3+)") (class "Default")
      (node (ref "R58") (pin "2") (pinfunction "2_2") (pintype "passive"))
      (node (ref "R59") (pin "1") (pinfunction "1_1") (pintype "passive"))
      (node (ref "U8") (pin "10") (pinfunction "IN3+_10") (pintype "input"))
    )
    (net (code "39") (name "Net-(U8C-IN3-)") (class "Default")
      (node (ref "R81") (pin "2") (pinfunction "2_2") (pintype "passive"))
      (node (ref "R83") (pin "2") (pinfunction "2_2") (pintype "passive"))
      (node (ref "U8") (pin "9") (pinfunction "IN3-_9") (pintype "input"))
    )
    (net (code "40") (name "Net-(U8C-OUT3)") (class "Default")
      (node (ref "R57") (pin "1") (pinfunction "1_1") (pintype "passive"))
      (node (ref "R81") (pin "1") (pinfunction "1_1") (pintype "passive"))
      (node (ref "U8") (pin "8") (pinfunction "OUT3_8") (pintype "output"))
    )
    (net (code "41") (name "Net-(U8D-IN4+)") (class "Default")
      (node (ref "R68") (pin "2") (pinfunction "2_2") (pintype "passive"))
      (node (ref "R70") (pin "1") (pinfunction "1_1") (pintype "passive"))
      (node (ref "U8") (pin "12") (pinfunction "IN4+_12") (pintype "input"))
    )
    (net (code "42") (name "Net-(U8D-IN4-)") (class "Default")
      (node (ref "R85") (pin "2") (pinfunction "2_2") (pintype "passive"))
      (node (ref "R87") (pin "2") (pinfunction "2_2") (pintype "passive"))
      (node (ref "U8") (pin "13") (pinfunction "IN4-_13") (pintype "input"))
    )
    (net (code "43") (name "Net-(U8D-OUT4)") (class "Default")
      (node (ref "R67") (pin "1") (pinfunction "1_1") (pintype "passive"))
      (node (ref "R85") (pin "1") (pinfunction "1_1") (pintype "passive"))
      (node (ref "U8") (pin "14") (pinfunction "OUT4_14") (pintype "output"))
    )
  )
)
